# BpodFSM_r2_1.net
KiCad netlist of a schematic drawn in EAGLE
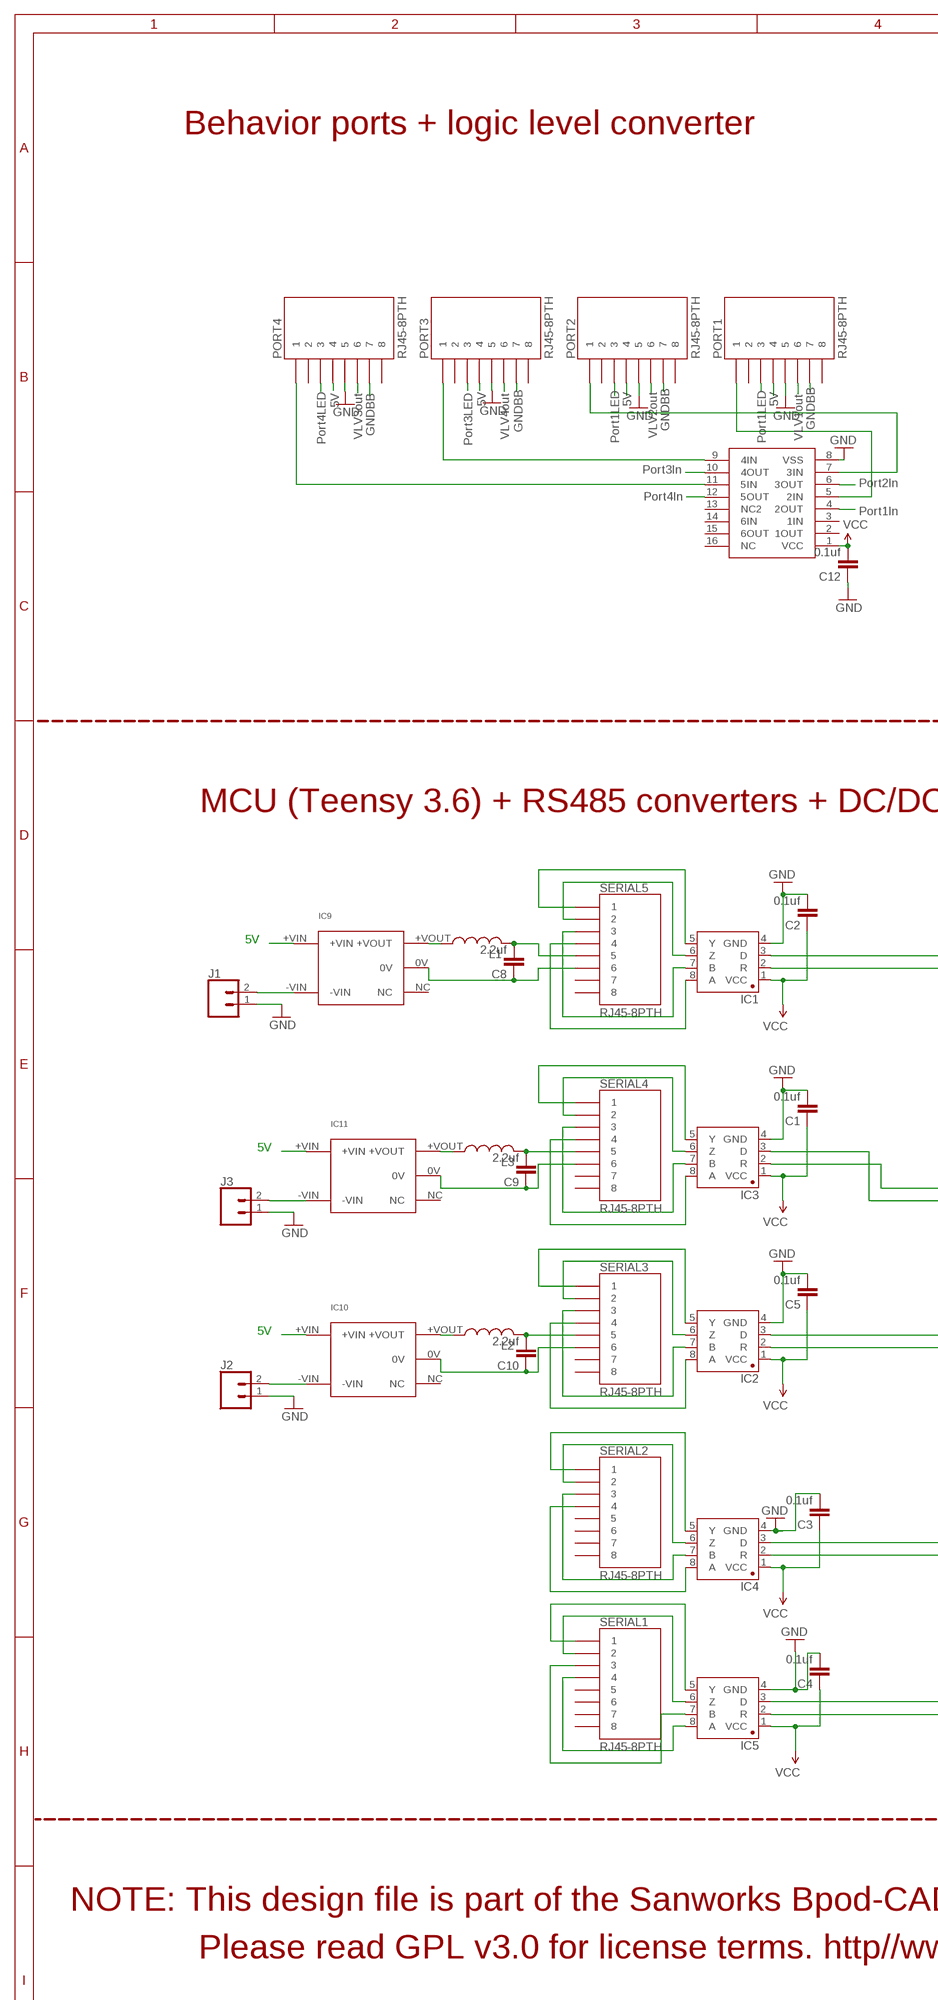
[diagram p0: schematic, sheet 1, part 1 of 2]
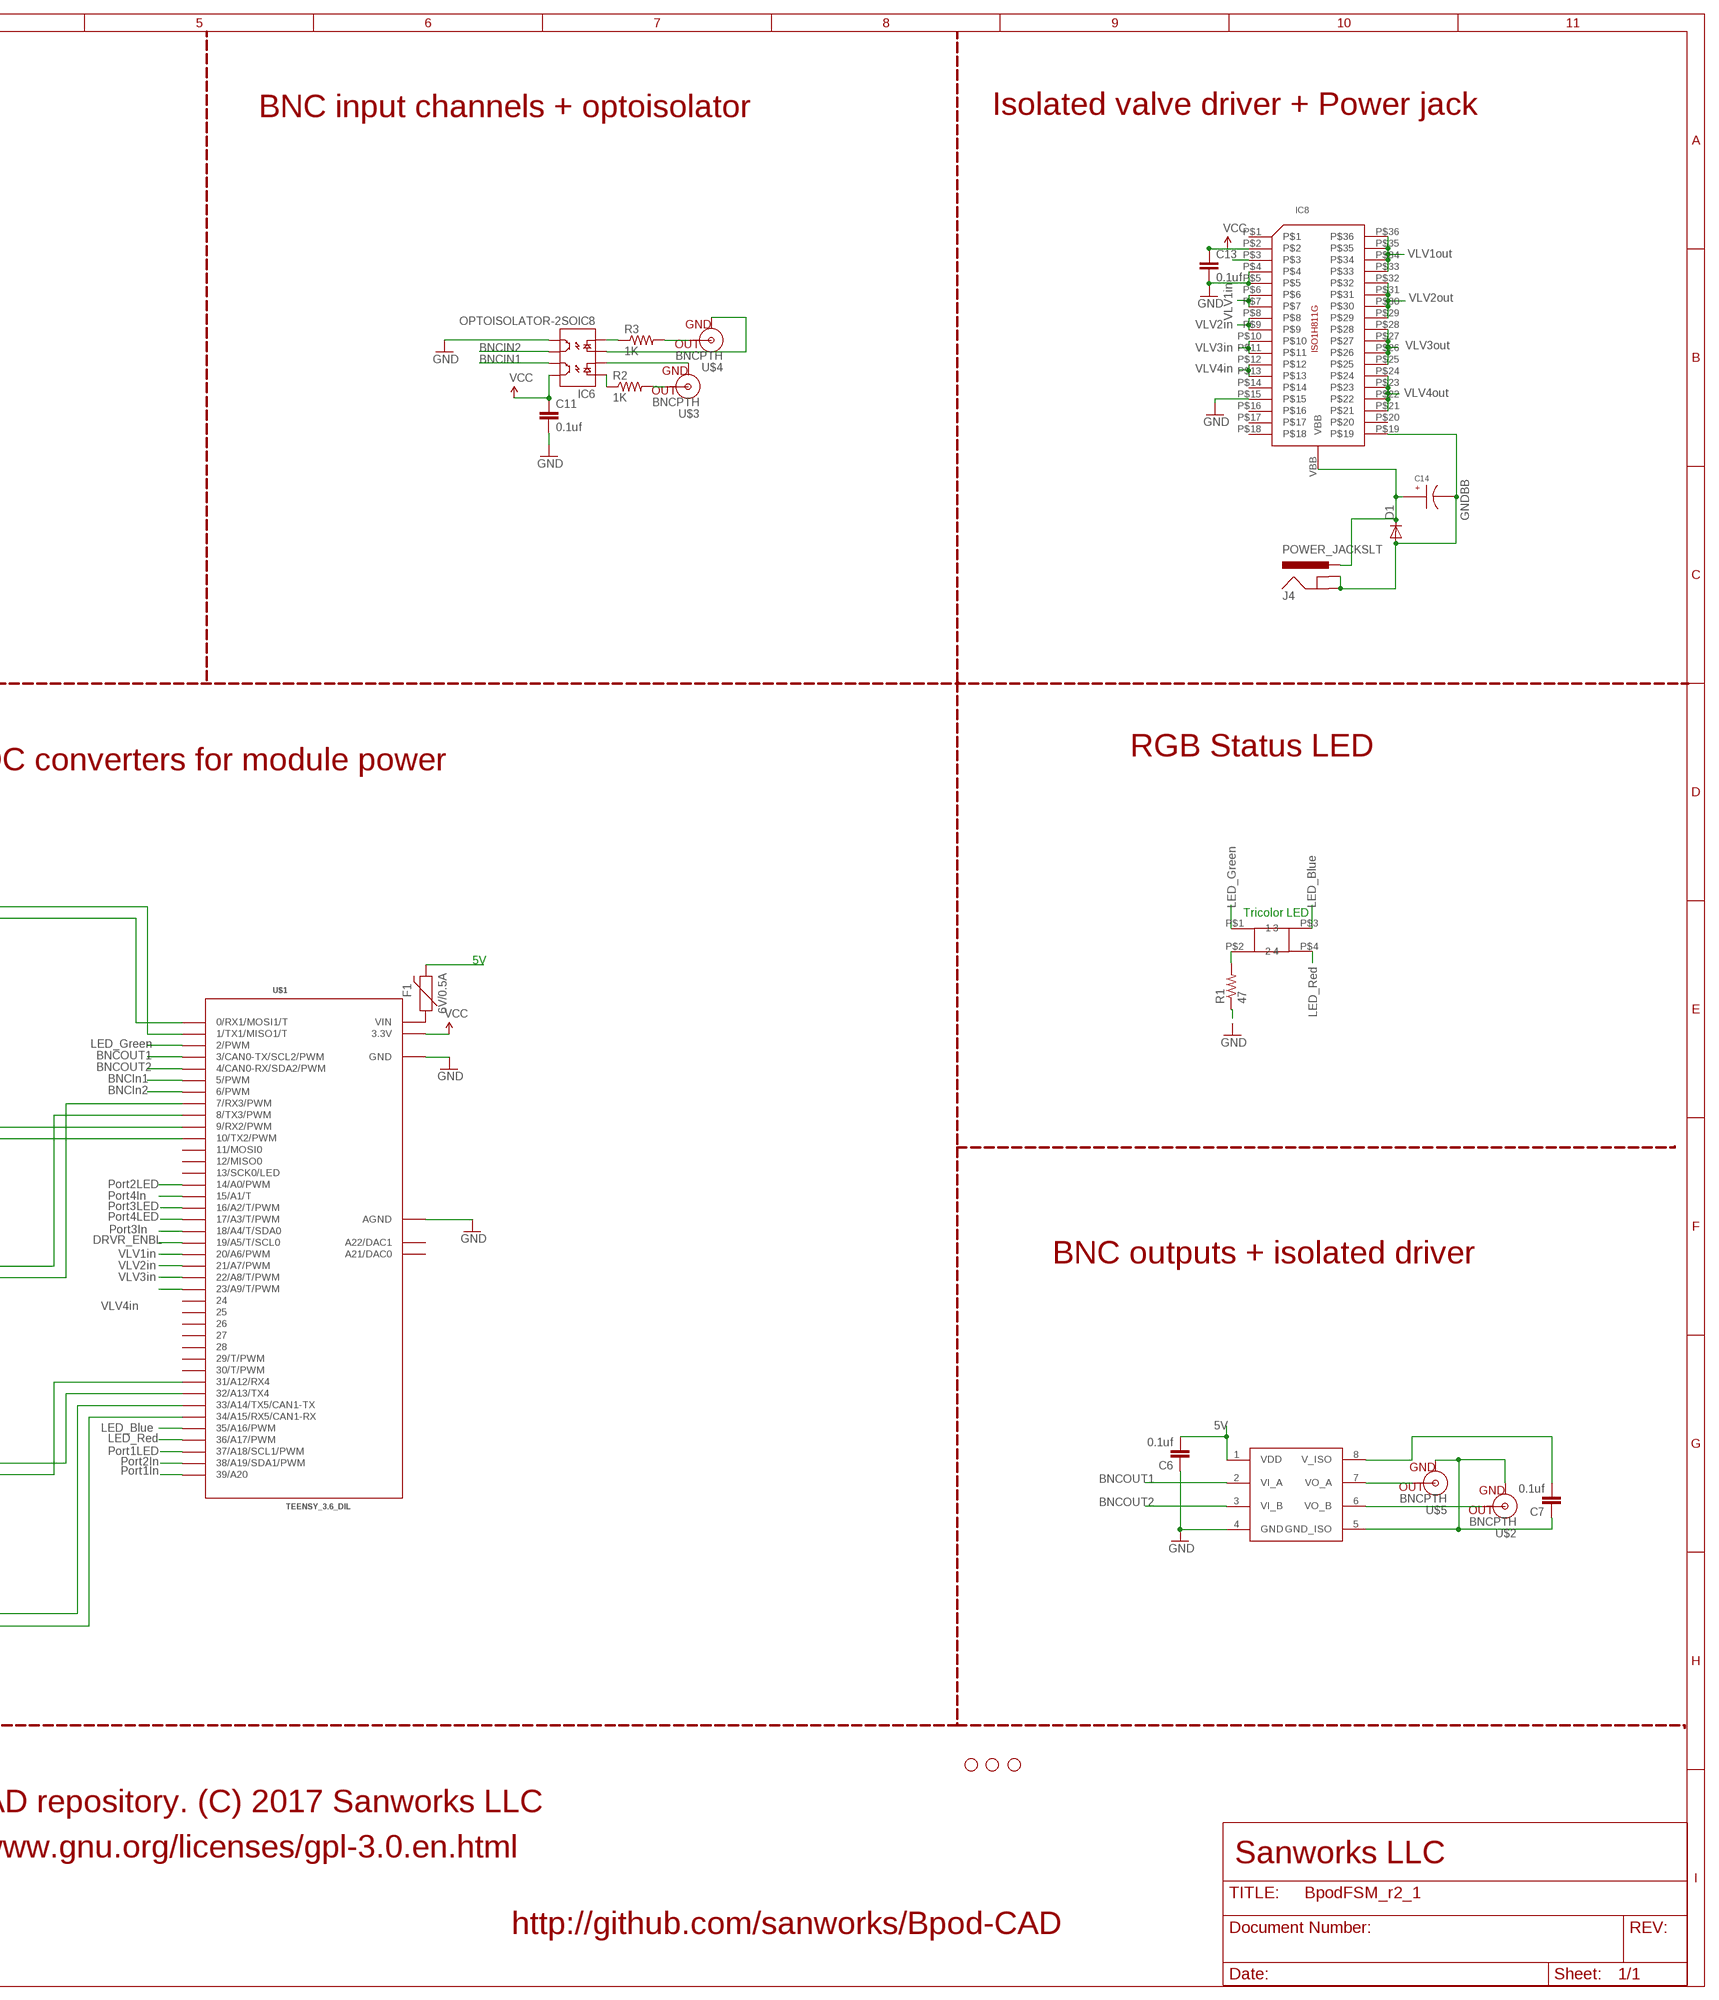
[diagram p1: schematic, sheet 1, part 2 of 2]

(export (version "E")
  (design (tool "Eeschema 10.0.6"))
  (components
    (comp (ref "C1")
      (value "0.1uf")
      (footprint "eagle-import:1206")
      (libsource (lib "eagle-import") (part "CAP1206"))
    )
    (comp (ref "C2")
      (value "0.1uf")
      (footprint "eagle-import:1206")
      (libsource (lib "eagle-import") (part "CAP1206"))
    )
    (comp (ref "C3")
      (value "0.1uf")
      (footprint "eagle-import:1206")
      (libsource (lib "eagle-import") (part "CAP1206"))
    )
    (comp (ref "C4")
      (value "0.1uf")
      (footprint "eagle-import:1206")
      (libsource (lib "eagle-import") (part "CAP1206"))
    )
    (comp (ref "C5")
      (value "0.1uf")
      (footprint "eagle-import:1206")
      (libsource (lib "eagle-import") (part "CAP1206"))
    )
    (comp (ref "C6")
      (value "0.1uf")
      (footprint "eagle-import:1206")
      (libsource (lib "eagle-import") (part "CAP1206"))
    )
    (comp (ref "C7")
      (value "0.1uf")
      (footprint "eagle-import:1206")
      (libsource (lib "eagle-import") (part "CAP1206"))
    )
    (comp (ref "C8")
      (value "2.2uf")
      (footprint "eagle-import:1206")
      (libsource (lib "eagle-import") (part "CAP1206"))
    )
    (comp (ref "C9")
      (value "2.2uf")
      (footprint "eagle-import:1206")
      (libsource (lib "eagle-import") (part "CAP1206"))
    )
    (comp (ref "C10")
      (value "2.2uf")
      (footprint "eagle-import:1206")
      (libsource (lib "eagle-import") (part "CAP1206"))
    )
    (comp (ref "C11")
      (value "0.1uf")
      (footprint "eagle-import:1206")
      (libsource (lib "eagle-import") (part "CAP1206"))
    )
    (comp (ref "C12")
      (value "0.1uf")
      (footprint "eagle-import:1206")
      (libsource (lib "eagle-import") (part "CAP1206"))
    )
    (comp (ref "C13")
      (value "0.1uf")
      (footprint "eagle-import:1206")
      (libsource (lib "eagle-import") (part "CAP1206"))
    )
    (comp (ref "C14")
      (value "EEE-FK1H100UR")
      (footprint "eagle-import:EEE-FK1H100UR")
      (libsource (lib "eagle-import") (part "EEE-FK1H100UR"))
    )
    (comp (ref "D1")
      (value "DIODE-DO214AA")
      (footprint "eagle-import:DO214AA")
      (libsource (lib "eagle-import") (part "DIODE-DO214AA"))
    )
    (comp (ref "F1")
      (value "6V/0.5A")
      (footprint "eagle-import:1206")
      (libsource (lib "eagle-import") (part "PPTC_HALF-AMP"))
    )
    (comp (ref "IC1")
      (value "SN65HVD31DR")
      (footprint "eagle-import:SO08")
      (libsource (lib "eagle-import") (part "SN65HVD31DR"))
    )
    (comp (ref "IC2")
      (value "SN65HVD31DR")
      (footprint "eagle-import:SO08")
      (libsource (lib "eagle-import") (part "SN65HVD31DR"))
    )
    (comp (ref "IC3")
      (value "SN65HVD31DR")
      (footprint "eagle-import:SO08")
      (libsource (lib "eagle-import") (part "SN65HVD31DR"))
    )
    (comp (ref "IC4")
      (value "SN65HVD31DR")
      (footprint "eagle-import:SO08")
      (libsource (lib "eagle-import") (part "SN65HVD31DR"))
    )
    (comp (ref "IC5")
      (value "SN65HVD31DR")
      (footprint "eagle-import:SO08")
      (libsource (lib "eagle-import") (part "SN65HVD31DR"))
    )
    (comp (ref "IC6")
      (value "OPTOISOLATOR-2SOIC8")
      (footprint "eagle-import:SO08-2")
      (libsource (lib "eagle-import") (part "OPTOISOLATOR-2SOIC8"))
    )
    (comp (ref "IC7")
      (value "ADUM5240")
      (footprint "eagle-import:SO08")
      (libsource (lib "eagle-import") (part "ADUM5240"))
    )
    (comp (ref "IC8")
      (value "ISO1H811G")
      (footprint "eagle-import:ISO1H811G")
      (libsource (lib "eagle-import") (part "ISO1H811G"))
    )
    (comp (ref "IC9")
      (value "MTU1D0505MC")
      (footprint "eagle-import:MTU1D0505MC")
      (libsource (lib "eagle-import") (part "MTU1D0505MC"))
    )
    (comp (ref "IC10")
      (value "MTU1D0505MC")
      (footprint "eagle-import:MTU1D0505MC")
      (libsource (lib "eagle-import") (part "MTU1D0505MC"))
    )
    (comp (ref "IC11")
      (value "MTU1D0505MC")
      (footprint "eagle-import:MTU1D0505MC")
      (libsource (lib "eagle-import") (part "MTU1D0505MC"))
    )
    (comp (ref "IC12")
      (value "CD4050")
      (footprint "eagle-import:SO16")
      (libsource (lib "eagle-import") (part "CD4050"))
    )
    (comp (ref "J1")
      (value "CONN_02")
      (footprint "eagle-import:1X02")
      (libsource (lib "eagle-import") (part "CONN_02"))
    )
    (comp (ref "J2")
      (value "CONN_02")
      (footprint "eagle-import:1X02")
      (libsource (lib "eagle-import") (part "CONN_02"))
    )
    (comp (ref "J3")
      (value "CONN_02")
      (footprint "eagle-import:1X02")
      (libsource (lib "eagle-import") (part "CONN_02"))
    )
    (comp (ref "J4")
      (value "POWER_JACKSLT")
      (footprint "eagle-import:POWER_JACK_SLOT")
      (libsource (lib "eagle-import") (part "POWER_JACKSLT"))
    )
    (comp (ref "JP3")
      (value "STAND-OFF")
      (footprint "eagle-import:STAND-OFF")
      (libsource (lib "eagle-import") (part "STAND-OFF"))
    )
    (comp (ref "JP4")
      (value "STAND-OFF")
      (footprint "eagle-import:STAND-OFF")
      (libsource (lib "eagle-import") (part "STAND-OFF"))
    )
    (comp (ref "JP5")
      (value "STAND-OFF")
      (footprint "eagle-import:STAND-OFF")
      (libsource (lib "eagle-import") (part "STAND-OFF"))
    )
    (comp (ref "L1")
      (value "L-USL3225M")
      (footprint "eagle-import:L3225M")
      (libsource (lib "eagle-import") (part "L-USL3225M"))
    )
    (comp (ref "L2")
      (value "L-USL3225M")
      (footprint "eagle-import:L3225M")
      (libsource (lib "eagle-import") (part "L-USL3225M"))
    )
    (comp (ref "L3")
      (value "L-USL3225M")
      (footprint "eagle-import:L3225M")
      (libsource (lib "eagle-import") (part "L-USL3225M"))
    )
    (comp (ref "PORT1")
      (value "RJ45-8PTH")
      (footprint "eagle-import:RJ45-8")
      (libsource (lib "eagle-import") (part "RJ45-8PTH"))
    )
    (comp (ref "PORT2")
      (value "RJ45-8PTH")
      (footprint "eagle-import:RJ45-8")
      (libsource (lib "eagle-import") (part "RJ45-8PTH"))
    )
    (comp (ref "PORT3")
      (value "RJ45-8PTH")
      (footprint "eagle-import:RJ45-8")
      (libsource (lib "eagle-import") (part "RJ45-8PTH"))
    )
    (comp (ref "PORT4")
      (value "RJ45-8PTH")
      (footprint "eagle-import:RJ45-8")
      (libsource (lib "eagle-import") (part "RJ45-8PTH"))
    )
    (comp (ref "R1")
      (value "47")
      (footprint "eagle-import:1206")
      (libsource (lib "eagle-import") (part "RESISTOR1206"))
    )
    (comp (ref "R2")
      (value "1K")
      (footprint "eagle-import:1206")
      (libsource (lib "eagle-import") (part "SparkFun-Resistors_RESISTOR1206"))
    )
    (comp (ref "R3")
      (value "1K")
      (footprint "eagle-import:1206")
      (libsource (lib "eagle-import") (part "SparkFun-Resistors_RESISTOR1206"))
    )
    (comp (ref "SERIAL1")
      (value "RJ45-8PTH")
      (footprint "eagle-import:RJ45-8")
      (libsource (lib "eagle-import") (part "RJ45-8PTH"))
    )
    (comp (ref "SERIAL2")
      (value "RJ45-8PTH")
      (footprint "eagle-import:RJ45-8")
      (libsource (lib "eagle-import") (part "RJ45-8PTH"))
    )
    (comp (ref "SERIAL3")
      (value "RJ45-8PTH")
      (footprint "eagle-import:RJ45-8")
      (libsource (lib "eagle-import") (part "RJ45-8PTH"))
    )
    (comp (ref "SERIAL4")
      (value "RJ45-8PTH")
      (footprint "eagle-import:RJ45-8")
      (libsource (lib "eagle-import") (part "RJ45-8PTH"))
    )
    (comp (ref "SERIAL5")
      (value "RJ45-8PTH")
      (footprint "eagle-import:RJ45-8")
      (libsource (lib "eagle-import") (part "RJ45-8PTH"))
    )
    (comp (ref "U$1")
      (value "TEENSY_3.6_DIL")
      (footprint "eagle-import:TEENSY_3.6_DIL")
      (libsource (lib "eagle-import") (part "TEENSY_3.6_DIL"))
    )
    (comp (ref "U$2")
      (value "BNCPTH")
      (footprint "eagle-import:BNC")
      (libsource (lib "eagle-import") (part "BNCPTH"))
    )
    (comp (ref "U$3")
      (value "BNCPTH")
      (footprint "eagle-import:BNC")
      (libsource (lib "eagle-import") (part "BNCPTH"))
    )
    (comp (ref "U$4")
      (value "BNCPTH")
      (footprint "eagle-import:BNC")
      (libsource (lib "eagle-import") (part "BNCPTH"))
    )
    (comp (ref "U$5")
      (value "BNCPTH")
      (footprint "eagle-import:BNC")
      (libsource (lib "eagle-import") (part "BNCPTH"))
    )
    (comp (ref "U$8")
      (value "SQUARE_TRICOLOR_LED")
      (footprint "eagle-import:SQUARE_TRICOLOR_LED")
      (libsource (lib "eagle-import") (part "SQUARE_TRICOLOR_LED"))
    )
  )
  (nets
    (net (code "1") (name "/5V") (class "Default")
      (node (ref "C6") (pin "2") (pinfunction "2_2") (pintype "passive"))
      (node (ref "F1") (pin "2") (pinfunction "2_2") (pintype "bidirectional"))
      (node (ref "IC10") (pin "+VIN") (pinfunction "+VIN_+VIN") (pintype "bidirectional"))
      (node (ref "IC11") (pin "+VIN") (pinfunction "+VIN_+VIN") (pintype "bidirectional"))
      (node (ref "IC7") (pin "1") (pinfunction "VDD_1") (pintype "bidirectional"))
      (node (ref "IC9") (pin "+VIN") (pinfunction "+VIN_+VIN") (pintype "bidirectional"))
      (node (ref "PORT1") (pin "4") (pinfunction "4_4") (pintype "bidirectional"))
      (node (ref "PORT2") (pin "4") (pinfunction "4_4") (pintype "bidirectional"))
      (node (ref "PORT3") (pin "4") (pinfunction "4_4") (pintype "bidirectional"))
      (node (ref "PORT4") (pin "4") (pinfunction "4_4") (pintype "bidirectional"))
    )
    (net (code "2") (name "/BNCIN1") (class "Default")
      (node (ref "IC6") (pin "7") (pinfunction "EM1_7") (pintype "bidirectional"))
      (node (ref "U$1") (pin "6") (pinfunction "6/PWM_6") (pintype "bidirectional"))
    )
    (net (code "3") (name "/BNCIN2") (class "Default")
      (node (ref "IC6") (pin "6") (pinfunction "CL2_6") (pintype "bidirectional"))
      (node (ref "U$1") (pin "5") (pinfunction "5/PWM_5") (pintype "bidirectional"))
    )
    (net (code "4") (name "/BNCOUT1") (class "Default")
      (node (ref "IC7") (pin "3") (pinfunction "VI_B_3") (pintype "bidirectional"))
      (node (ref "U$1") (pin "4") (pinfunction "4/CAN0-RX/SDA2/PWM_4") (pintype "bidirectional"))
    )
    (net (code "5") (name "/BNCOUT2") (class "Default")
      (node (ref "IC7") (pin "2") (pinfunction "VI_A_2") (pintype "bidirectional"))
      (node (ref "U$1") (pin "3") (pinfunction "3/CAN0-TX/SCL2/PWM_3") (pintype "bidirectional"))
    )
    (net (code "6") (name "/DRVR_ENBL") (class "Default")
      (node (ref "IC8") (pin "P$3") (pinfunction "P$3_P$3") (pintype "bidirectional"))
      (node (ref "U$1") (pin "19/A5") (pinfunction "19/A5/T/SCL0_19/A5") (pintype "bidirectional"))
    )
    (net (code "7") (name "/GNDBB") (class "Default")
      (node (ref "C14") (pin "CATHODE") (pinfunction "CATHODE_CATHODE") (pintype "bidirectional"))
      (node (ref "D1") (pin "A") (pinfunction "A_A") (pintype "passive"))
      (node (ref "IC8") (pin "P$19") (pinfunction "P$19_P$19") (pintype "bidirectional"))
      (node (ref "J4") (pin "GND@1") (pinfunction "GNDBREAK_GND@1") (pintype "bidirectional"))
      (node (ref "J4") (pin "GND@2") (pinfunction "GND_GND@2") (pintype "bidirectional"))
      (node (ref "PORT1") (pin "7") (pinfunction "7_7") (pintype "bidirectional"))
      (node (ref "PORT2") (pin "7") (pinfunction "7_7") (pintype "bidirectional"))
      (node (ref "PORT3") (pin "7") (pinfunction "7_7") (pintype "bidirectional"))
      (node (ref "PORT4") (pin "7") (pinfunction "7_7") (pintype "bidirectional"))
    )
    (net (code "8") (name "/LED_BLUE") (class "Default")
      (node (ref "U$1") (pin "35/A16") (pinfunction "35/A16/PWM_35/A16") (pintype "bidirectional"))
      (node (ref "U$8") (pin "P$3") (pinfunction "3_P$3") (pintype "bidirectional"))
    )
    (net (code "9") (name "/LED_GREEN") (class "Default")
      (node (ref "U$1") (pin "2") (pinfunction "2/PWM_2") (pintype "bidirectional"))
      (node (ref "U$8") (pin "P$1") (pinfunction "1_P$1") (pintype "bidirectional"))
    )
    (net (code "10") (name "/LED_RED") (class "Default")
      (node (ref "U$1") (pin "36/A17") (pinfunction "36/A17/PWM_36/A17") (pintype "bidirectional"))
      (node (ref "U$8") (pin "P$4") (pinfunction "4_P$4") (pintype "bidirectional"))
    )
    (net (code "11") (name "/PORT1IN") (class "Default")
      (node (ref "IC12") (pin "4") (pinfunction "2OUT_4") (pintype "bidirectional"))
      (node (ref "U$1") (pin "39/A20") (pinfunction "39/A20_39/A20") (pintype "bidirectional"))
    )
    (net (code "12") (name "/PORT1LED") (class "Default")
      (node (ref "PORT1") (pin "3") (pinfunction "3_3") (pintype "bidirectional"))
      (node (ref "U$1") (pin "37/A18") (pinfunction "37/A18/SCL1/PWM_37/A18") (pintype "bidirectional"))
    )
    (net (code "13") (name "/PORT2IN") (class "Default")
      (node (ref "IC12") (pin "6") (pinfunction "3OUT_6") (pintype "bidirectional"))
      (node (ref "U$1") (pin "38/A19") (pinfunction "38/A19/SDA1/PWM_38/A19") (pintype "bidirectional"))
    )
    (net (code "14") (name "/PORT2LED") (class "Default")
      (node (ref "PORT2") (pin "3") (pinfunction "3_3") (pintype "bidirectional"))
      (node (ref "U$1") (pin "14/A0") (pinfunction "14/A0/PWM_14/A0") (pintype "bidirectional"))
    )
    (net (code "15") (name "/PORT3IN") (class "Default")
      (node (ref "IC12") (pin "10") (pinfunction "4OUT_10") (pintype "bidirectional"))
      (node (ref "U$1") (pin "18/A4") (pinfunction "18/A4/T/SDA0_18/A4") (pintype "bidirectional"))
    )
    (net (code "16") (name "/PORT3LED") (class "Default")
      (node (ref "PORT3") (pin "3") (pinfunction "3_3") (pintype "bidirectional"))
      (node (ref "U$1") (pin "16/A2") (pinfunction "16/A2/T/PWM_16/A2") (pintype "bidirectional"))
    )
    (net (code "17") (name "/PORT4IN") (class "Default")
      (node (ref "IC12") (pin "12") (pinfunction "5OUT_12") (pintype "bidirectional"))
      (node (ref "U$1") (pin "15/A1") (pinfunction "15/A1/T_15/A1") (pintype "bidirectional"))
    )
    (net (code "18") (name "/PORT4LED") (class "Default")
      (node (ref "PORT4") (pin "3") (pinfunction "3_3") (pintype "bidirectional"))
      (node (ref "U$1") (pin "17/A3") (pinfunction "17/A3/T/PWM_17/A3") (pintype "bidirectional"))
    )
    (net (code "19") (name "/VLV1IN") (class "Default")
      (node (ref "IC8") (pin "P$6") (pinfunction "P$6_P$6") (pintype "bidirectional"))
      (node (ref "IC8") (pin "P$7") (pinfunction "P$7_P$7") (pintype "bidirectional"))
      (node (ref "U$1") (pin "23/A9") (pinfunction "23/A9/T/PWM_23/A9") (pintype "bidirectional"))
    )
    (net (code "20") (name "/VLV1OUT") (class "Default")
      (node (ref "IC8") (pin "P$33") (pinfunction "P$33_P$33") (pintype "bidirectional"))
      (node (ref "IC8") (pin "P$34") (pinfunction "P$34_P$34") (pintype "bidirectional"))
      (node (ref "IC8") (pin "P$35") (pinfunction "P$35_P$35") (pintype "bidirectional"))
      (node (ref "IC8") (pin "P$36") (pinfunction "P$36_P$36") (pintype "bidirectional"))
      (node (ref "PORT1") (pin "6") (pinfunction "6_6") (pintype "bidirectional"))
    )
    (net (code "21") (name "/VLV2IN") (class "Default")
      (node (ref "IC8") (pin "P$8") (pinfunction "P$8_P$8") (pintype "bidirectional"))
      (node (ref "IC8") (pin "P$9") (pinfunction "P$9_P$9") (pintype "bidirectional"))
      (node (ref "U$1") (pin "22/A8") (pinfunction "22/A8/T/PWM_22/A8") (pintype "bidirectional"))
    )
    (net (code "22") (name "/VLV2OUT") (class "Default")
      (node (ref "IC8") (pin "P$29") (pinfunction "P$29_P$29") (pintype "bidirectional"))
      (node (ref "IC8") (pin "P$30") (pinfunction "P$30_P$30") (pintype "bidirectional"))
      (node (ref "IC8") (pin "P$31") (pinfunction "P$31_P$31") (pintype "bidirectional"))
      (node (ref "IC8") (pin "P$32") (pinfunction "P$32_P$32") (pintype "bidirectional"))
      (node (ref "PORT2") (pin "6") (pinfunction "6_6") (pintype "bidirectional"))
    )
    (net (code "23") (name "/VLV3IN") (class "Default")
      (node (ref "IC8") (pin "P$12") (pinfunction "P$12_P$12") (pintype "bidirectional"))
      (node (ref "IC8") (pin "P$13") (pinfunction "P$13_P$13") (pintype "bidirectional"))
      (node (ref "U$1") (pin "20/A6") (pinfunction "20/A6/PWM_20/A6") (pintype "bidirectional"))
    )
    (net (code "24") (name "/VLV3OUT") (class "Default")
      (node (ref "IC8") (pin "P$21") (pinfunction "P$21_P$21") (pintype "bidirectional"))
      (node (ref "IC8") (pin "P$22") (pinfunction "P$22_P$22") (pintype "bidirectional"))
      (node (ref "IC8") (pin "P$23") (pinfunction "P$23_P$23") (pintype "bidirectional"))
      (node (ref "IC8") (pin "P$24") (pinfunction "P$24_P$24") (pintype "bidirectional"))
      (node (ref "PORT3") (pin "6") (pinfunction "6_6") (pintype "bidirectional"))
    )
    (net (code "25") (name "/VLV4IN") (class "Default")
      (node (ref "IC8") (pin "P$10") (pinfunction "P$10_P$10") (pintype "bidirectional"))
      (node (ref "IC8") (pin "P$11") (pinfunction "P$11_P$11") (pintype "bidirectional"))
      (node (ref "U$1") (pin "21/A7") (pinfunction "21/A7/PWM_21/A7") (pintype "bidirectional"))
    )
    (net (code "26") (name "/VLV4OUT") (class "Default")
      (node (ref "IC8") (pin "P$25") (pinfunction "P$25_P$25") (pintype "bidirectional"))
      (node (ref "IC8") (pin "P$26") (pinfunction "P$26_P$26") (pintype "bidirectional"))
      (node (ref "IC8") (pin "P$27") (pinfunction "P$27_P$27") (pintype "bidirectional"))
      (node (ref "IC8") (pin "P$28") (pinfunction "P$28_P$28") (pintype "bidirectional"))
      (node (ref "PORT4") (pin "6") (pinfunction "6_6") (pintype "bidirectional"))
    )
    (net (code "27") (name "GND") (class "Default")
      (node (ref "C1") (pin "2") (pinfunction "2_2") (pintype "passive"))
      (node (ref "C11") (pin "2") (pinfunction "2_2") (pintype "passive"))
      (node (ref "C12") (pin "1") (pinfunction "1_1") (pintype "passive"))
      (node (ref "C13") (pin "2") (pinfunction "2_2") (pintype "passive"))
      (node (ref "C2") (pin "2") (pinfunction "2_2") (pintype "passive"))
      (node (ref "C3") (pin "2") (pinfunction "2_2") (pintype "passive"))
      (node (ref "C4") (pin "2") (pinfunction "2_2") (pintype "passive"))
      (node (ref "C5") (pin "2") (pinfunction "2_2") (pintype "passive"))
      (node (ref "C6") (pin "1") (pinfunction "1_1") (pintype "passive"))
      (node (ref "IC1") (pin "4") (pinfunction "GND_4") (pintype "bidirectional"))
      (node (ref "IC12") (pin "8") (pinfunction "VSS_8") (pintype "bidirectional"))
      (node (ref "IC2") (pin "4") (pinfunction "GND_4") (pintype "bidirectional"))
      (node (ref "IC3") (pin "4") (pinfunction "GND_4") (pintype "bidirectional"))
      (node (ref "IC4") (pin "4") (pinfunction "GND_4") (pintype "bidirectional"))
      (node (ref "IC5") (pin "4") (pinfunction "GND_4") (pintype "bidirectional"))
      (node (ref "IC6") (pin "5") (pinfunction "EM2_5") (pintype "bidirectional"))
      (node (ref "IC7") (pin "4") (pinfunction "GND_4") (pintype "bidirectional"))
      (node (ref "IC8") (pin "P$15") (pinfunction "P$15_P$15") (pintype "bidirectional"))
      (node (ref "IC8") (pin "P$4") (pinfunction "P$4_P$4") (pintype "bidirectional"))
      (node (ref "IC8") (pin "P$5") (pinfunction "P$5_P$5") (pintype "bidirectional"))
      (node (ref "J1") (pin "1") (pinfunction "1_1") (pintype "passive"))
      (node (ref "J2") (pin "1") (pinfunction "1_1") (pintype "passive"))
      (node (ref "J3") (pin "1") (pinfunction "1_1") (pintype "passive"))
      (node (ref "PORT1") (pin "5") (pinfunction "5_5") (pintype "bidirectional"))
      (node (ref "PORT2") (pin "5") (pinfunction "5_5") (pintype "bidirectional"))
      (node (ref "PORT3") (pin "5") (pinfunction "5_5") (pintype "bidirectional"))
      (node (ref "PORT4") (pin "5") (pinfunction "5_5") (pintype "bidirectional"))
      (node (ref "R1") (pin "1") (pinfunction "1_1") (pintype "passive"))
      (node (ref "U$1") (pin "AGND") (pinfunction "AGND_AGND") (pintype "power_in"))
      (node (ref "U$1") (pin "GND") (pinfunction "GND_GND") (pintype "power_in"))
      (node (ref "U$1") (pin "GND1") (pinfunction "GND_GND1") (pintype "power_in"))
    )
    (net (code "28") (name "Net-(C8-Pad1)") (class "Default")
      (node (ref "C8") (pin "1") (pinfunction "1_1") (pintype "passive"))
      (node (ref "IC9") (pin "0V") (pinfunction "0V_0V") (pintype "bidirectional"))
      (node (ref "SERIAL5") (pin "6") (pinfunction "6_6") (pintype "bidirectional"))
    )
    (net (code "29") (name "Net-(C8-Pad2)") (class "Default")
      (node (ref "C8") (pin "2") (pinfunction "2_2") (pintype "passive"))
      (node (ref "L1") (pin "2") (pinfunction "2_2") (pintype "passive"))
      (node (ref "SERIAL5") (pin "5") (pinfunction "5_5") (pintype "bidirectional"))
    )
    (net (code "30") (name "Net-(C9-Pad1)") (class "Default")
      (node (ref "C9") (pin "1") (pinfunction "1_1") (pintype "passive"))
      (node (ref "IC11") (pin "0V") (pinfunction "0V_0V") (pintype "bidirectional"))
      (node (ref "SERIAL4") (pin "6") (pinfunction "6_6") (pintype "bidirectional"))
    )
    (net (code "31") (name "Net-(C9-Pad2)") (class "Default")
      (node (ref "C9") (pin "2") (pinfunction "2_2") (pintype "passive"))
      (node (ref "L3") (pin "2") (pinfunction "2_2") (pintype "passive"))
      (node (ref "SERIAL4") (pin "5") (pinfunction "5_5") (pintype "bidirectional"))
    )
    (net (code "32") (name "Net-(C10-Pad1)") (class "Default")
      (node (ref "C10") (pin "1") (pinfunction "1_1") (pintype "passive"))
      (node (ref "IC10") (pin "0V") (pinfunction "0V_0V") (pintype "bidirectional"))
      (node (ref "SERIAL3") (pin "6") (pinfunction "6_6") (pintype "bidirectional"))
    )
    (net (code "33") (name "Net-(C10-Pad2)") (class "Default")
      (node (ref "C10") (pin "2") (pinfunction "2_2") (pintype "passive"))
      (node (ref "L2") (pin "2") (pinfunction "2_2") (pintype "passive"))
      (node (ref "SERIAL3") (pin "5") (pinfunction "5_5") (pintype "bidirectional"))
    )
    (net (code "34") (name "Net-(C14-PadANODE)") (class "Default")
      (node (ref "C14") (pin "ANODE") (pinfunction "ANODE_ANODE") (pintype "bidirectional"))
      (node (ref "D1") (pin "C") (pinfunction "C_C") (pintype "passive"))
      (node (ref "IC8") (pin "VBB") (pinfunction "VBB_VBB") (pintype "bidirectional"))
      (node (ref "J4") (pin "PWR") (pinfunction "PWR_PWR") (pintype "bidirectional"))
    )
    (net (code "35") (name "Net-(F1-Pad1)") (class "Default")
      (node (ref "F1") (pin "1") (pinfunction "1_1") (pintype "bidirectional"))
      (node (ref "U$1") (pin "VIN") (pinfunction "VIN_VIN") (pintype "power_in"))
    )
    (net (code "36") (name "Net-(IC1-A)") (class "Default")
      (node (ref "IC1") (pin "8") (pinfunction "A_8") (pintype "bidirectional"))
      (node (ref "SERIAL5") (pin "4") (pinfunction "4_4") (pintype "bidirectional"))
    )
    (net (code "37") (name "Net-(IC1-B)") (class "Default")
      (node (ref "IC1") (pin "7") (pinfunction "B_7") (pintype "bidirectional"))
      (node (ref "SERIAL5") (pin "3") (pinfunction "3_3") (pintype "bidirectional"))
    )
    (net (code "38") (name "Net-(IC1-D)") (class "Default")
      (node (ref "IC1") (pin "3") (pinfunction "D_3") (pintype "bidirectional"))
      (node (ref "U$1") (pin "1") (pinfunction "1/TX1/MISO1/T_1") (pintype "bidirectional"))
    )
    (net (code "39") (name "Net-(IC1-R)") (class "Default")
      (node (ref "IC1") (pin "2") (pinfunction "R_2") (pintype "bidirectional"))
      (node (ref "U$1") (pin "0") (pinfunction "0/RX1/MOSI1/T_0") (pintype "bidirectional"))
    )
    (net (code "40") (name "Net-(IC1-Y)") (class "Default")
      (node (ref "IC1") (pin "5") (pinfunction "Y_5") (pintype "bidirectional"))
      (node (ref "SERIAL5") (pin "1") (pinfunction "1_1") (pintype "bidirectional"))
    )
    (net (code "41") (name "Net-(IC1-Z)") (class "Default")
      (node (ref "IC1") (pin "6") (pinfunction "Z_6") (pintype "bidirectional"))
      (node (ref "SERIAL5") (pin "2") (pinfunction "2_2") (pintype "bidirectional"))
    )
    (net (code "42") (name "Net-(IC2-A)") (class "Default")
      (node (ref "IC2") (pin "8") (pinfunction "A_8") (pintype "bidirectional"))
      (node (ref "SERIAL3") (pin "4") (pinfunction "4_4") (pintype "bidirectional"))
    )
    (net (code "43") (name "Net-(IC2-B)") (class "Default")
      (node (ref "IC2") (pin "7") (pinfunction "B_7") (pintype "bidirectional"))
      (node (ref "SERIAL3") (pin "3") (pinfunction "3_3") (pintype "bidirectional"))
    )
    (net (code "44") (name "Net-(IC2-D)") (class "Default")
      (node (ref "IC2") (pin "3") (pinfunction "D_3") (pintype "bidirectional"))
      (node (ref "U$1") (pin "8") (pinfunction "8/TX3/PWM_8") (pintype "bidirectional"))
    )
    (net (code "45") (name "Net-(IC2-R)") (class "Default")
      (node (ref "IC2") (pin "2") (pinfunction "R_2") (pintype "bidirectional"))
      (node (ref "U$1") (pin "7") (pinfunction "7/RX3/PWM_7") (pintype "bidirectional"))
    )
    (net (code "46") (name "Net-(IC2-Y)") (class "Default")
      (node (ref "IC2") (pin "5") (pinfunction "Y_5") (pintype "bidirectional"))
      (node (ref "SERIAL3") (pin "1") (pinfunction "1_1") (pintype "bidirectional"))
    )
    (net (code "47") (name "Net-(IC2-Z)") (class "Default")
      (node (ref "IC2") (pin "6") (pinfunction "Z_6") (pintype "bidirectional"))
      (node (ref "SERIAL3") (pin "2") (pinfunction "2_2") (pintype "bidirectional"))
    )
    (net (code "48") (name "Net-(IC3-A)") (class "Default")
      (node (ref "IC3") (pin "8") (pinfunction "A_8") (pintype "bidirectional"))
      (node (ref "SERIAL4") (pin "4") (pinfunction "4_4") (pintype "bidirectional"))
    )
    (net (code "49") (name "Net-(IC3-B)") (class "Default")
      (node (ref "IC3") (pin "7") (pinfunction "B_7") (pintype "bidirectional"))
      (node (ref "SERIAL4") (pin "3") (pinfunction "3_3") (pintype "bidirectional"))
    )
    (net (code "50") (name "Net-(IC3-D)") (class "Default")
      (node (ref "IC3") (pin "3") (pinfunction "D_3") (pintype "bidirectional"))
      (node (ref "U$1") (pin "10") (pinfunction "10/TX2/PWM_10") (pintype "bidirectional"))
    )
    (net (code "51") (name "Net-(IC3-R)") (class "Default")
      (node (ref "IC3") (pin "2") (pinfunction "R_2") (pintype "bidirectional"))
      (node (ref "U$1") (pin "9") (pinfunction "9/RX2/PWM_9") (pintype "bidirectional"))
    )
    (net (code "52") (name "Net-(IC3-Y)") (class "Default")
      (node (ref "IC3") (pin "5") (pinfunction "Y_5") (pintype "bidirectional"))
      (node (ref "SERIAL4") (pin "1") (pinfunction "1_1") (pintype "bidirectional"))
    )
    (net (code "53") (name "Net-(IC3-Z)") (class "Default")
      (node (ref "IC3") (pin "6") (pinfunction "Z_6") (pintype "bidirectional"))
      (node (ref "SERIAL4") (pin "2") (pinfunction "2_2") (pintype "bidirectional"))
    )
    (net (code "54") (name "Net-(IC4-A)") (class "Default")
      (node (ref "IC4") (pin "8") (pinfunction "A_8") (pintype "bidirectional"))
      (node (ref "SERIAL2") (pin "4") (pinfunction "4_4") (pintype "bidirectional"))
    )
    (net (code "55") (name "Net-(IC4-B)") (class "Default")
      (node (ref "IC4") (pin "7") (pinfunction "B_7") (pintype "bidirectional"))
      (node (ref "SERIAL2") (pin "3") (pinfunction "3_3") (pintype "bidirectional"))
    )
    (net (code "56") (name "Net-(IC4-D)") (class "Default")
      (node (ref "IC4") (pin "3") (pinfunction "D_3") (pintype "bidirectional"))
      (node (ref "U$1") (pin "32/A13") (pinfunction "32/A13/TX4_32/A13") (pintype "bidirectional"))
    )
    (net (code "57") (name "Net-(IC4-R)") (class "Default")
      (node (ref "IC4") (pin "2") (pinfunction "R_2") (pintype "bidirectional"))
      (node (ref "U$1") (pin "31/A12") (pinfunction "31/A12/RX4_31/A12") (pintype "bidirectional"))
    )
    (net (code "58") (name "Net-(IC4-Y)") (class "Default")
      (node (ref "IC4") (pin "5") (pinfunction "Y_5") (pintype "bidirectional"))
      (node (ref "SERIAL2") (pin "1") (pinfunction "1_1") (pintype "bidirectional"))
    )
    (net (code "59") (name "Net-(IC4-Z)") (class "Default")
      (node (ref "IC4") (pin "6") (pinfunction "Z_6") (pintype "bidirectional"))
      (node (ref "SERIAL2") (pin "2") (pinfunction "2_2") (pintype "bidirectional"))
    )
    (net (code "60") (name "Net-(IC5-A)") (class "Default")
      (node (ref "IC5") (pin "8") (pinfunction "A_8") (pintype "bidirectional"))
      (node (ref "SERIAL1") (pin "4") (pinfunction "4_4") (pintype "bidirectional"))
    )
    (net (code "61") (name "Net-(IC5-B)") (class "Default")
      (node (ref "IC5") (pin "7") (pinfunction "B_7") (pintype "bidirectional"))
      (node (ref "SERIAL1") (pin "3") (pinfunction "3_3") (pintype "bidirectional"))
    )
    (net (code "62") (name "Net-(IC5-D)") (class "Default")
      (node (ref "IC5") (pin "3") (pinfunction "D_3") (pintype "bidirectional"))
      (node (ref "U$1") (pin "33/A14") (pinfunction "33/A14/TX5/CAN1-TX_33/A14") (pintype "bidirectional"))
    )
    (net (code "63") (name "Net-(IC5-R)") (class "Default")
      (node (ref "IC5") (pin "2") (pinfunction "R_2") (pintype "bidirectional"))
      (node (ref "U$1") (pin "34/A15") (pinfunction "34/A15/RX5/CAN1-RX_34/A15") (pintype "bidirectional"))
    )
    (net (code "64") (name "Net-(IC5-Y)") (class "Default")
      (node (ref "IC5") (pin "5") (pinfunction "Y_5") (pintype "bidirectional"))
      (node (ref "SERIAL1") (pin "1") (pinfunction "1_1") (pintype "bidirectional"))
    )
    (net (code "65") (name "Net-(IC5-Z)") (class "Default")
      (node (ref "IC5") (pin "6") (pinfunction "Z_6") (pintype "bidirectional"))
      (node (ref "SERIAL1") (pin "2") (pinfunction "2_2") (pintype "bidirectional"))
    )
    (net (code "66") (name "Net-(IC6-A1)") (class "Default")
      (node (ref "IC6") (pin "1") (pinfunction "A1_1") (pintype "bidirectional"))
      (node (ref "R2") (pin "1") (pinfunction "1_1") (pintype "passive"))
    )
    (net (code "67") (name "Net-(IC6-A2)") (class "Default")
      (node (ref "IC6") (pin "3") (pinfunction "A2_3") (pintype "bidirectional"))
      (node (ref "U$4") (pin "GND") (pinfunction "GND_GND") (pintype "bidirectional"))
    )
    (net (code "68") (name "Net-(IC6-C1)") (class "Default")
      (node (ref "IC6") (pin "2") (pinfunction "C1_2") (pintype "bidirectional"))
      (node (ref "U$3") (pin "GND") (pinfunction "GND_GND") (pintype "bidirectional"))
    )
    (net (code "69") (name "Net-(IC6-C2)") (class "Default")
      (node (ref "IC6") (pin "4") (pinfunction "C2_4") (pintype "bidirectional"))
      (node (ref "R3") (pin "1") (pinfunction "1_1") (pintype "passive"))
    )
    (net (code "70") (name "Net-(IC7-GND_ISO)") (class "Default")
      (node (ref "C7") (pin "1") (pinfunction "1_1") (pintype "passive"))
      (node (ref "IC7") (pin "5") (pinfunction "GND_ISO_5") (pintype "bidirectional"))
      (node (ref "U$2") (pin "GND") (pinfunction "GND_GND") (pintype "bidirectional"))
      (node (ref "U$5") (pin "GND") (pinfunction "GND_GND") (pintype "bidirectional"))
    )
    (net (code "71") (name "Net-(IC7-VO_A)") (class "Default")
      (node (ref "IC7") (pin "7") (pinfunction "VO_A_7") (pintype "bidirectional"))
      (node (ref "U$5") (pin "S") (pinfunction "OUT_S") (pintype "bidirectional"))
    )
    (net (code "72") (name "Net-(IC7-VO_B)") (class "Default")
      (node (ref "IC7") (pin "6") (pinfunction "VO_B_6") (pintype "bidirectional"))
      (node (ref "U$2") (pin "S") (pinfunction "OUT_S") (pintype "bidirectional"))
    )
    (net (code "73") (name "Net-(IC7-V_ISO)") (class "Default")
      (node (ref "C7") (pin "2") (pinfunction "2_2") (pintype "passive"))
      (node (ref "IC7") (pin "8") (pinfunction "V_ISO_8") (pintype "bidirectional"))
    )
    (net (code "74") (name "Net-(IC9-Pad+VOUT)") (class "Default")
      (node (ref "IC9") (pin "+VOUT") (pinfunction "+VOUT_+VOUT") (pintype "bidirectional"))
      (node (ref "L1") (pin "1") (pinfunction "1_1") (pintype "passive"))
    )
    (net (code "75") (name "Net-(IC9-Pad-VIN)") (class "Default")
      (node (ref "IC9") (pin "-VIN") (pinfunction "-VIN_-VIN") (pintype "bidirectional"))
      (node (ref "J1") (pin "2") (pinfunction "2_2") (pintype "passive"))
    )
    (net (code "76") (name "Net-(IC10-Pad+VOUT)") (class "Default")
      (node (ref "IC10") (pin "+VOUT") (pinfunction "+VOUT_+VOUT") (pintype "bidirectional"))
      (node (ref "L2") (pin "1") (pinfunction "1_1") (pintype "passive"))
    )
    (net (code "77") (name "Net-(IC10-Pad-VIN)") (class "Default")
      (node (ref "IC10") (pin "-VIN") (pinfunction "-VIN_-VIN") (pintype "bidirectional"))
      (node (ref "J2") (pin "2") (pinfunction "2_2") (pintype "passive"))
    )
    (net (code "78") (name "Net-(IC11-Pad+VOUT)") (class "Default")
      (node (ref "IC11") (pin "+VOUT") (pinfunction "+VOUT_+VOUT") (pintype "bidirectional"))
      (node (ref "L3") (pin "1") (pinfunction "1_1") (pintype "passive"))
    )
    (net (code "79") (name "Net-(IC11-Pad-VIN)") (class "Default")
      (node (ref "IC11") (pin "-VIN") (pinfunction "-VIN_-VIN") (pintype "bidirectional"))
      (node (ref "J3") (pin "2") (pinfunction "2_2") (pintype "passive"))
    )
    (net (code "80") (name "Net-(IC12-2IN)") (class "Default")
      (node (ref "IC12") (pin "5") (pinfunction "2IN_5") (pintype "bidirectional"))
      (node (ref "PORT1") (pin "1") (pinfunction "1_1") (pintype "bidirectional"))
    )
    (net (code "81") (name "Net-(IC12-3IN)") (class "Default")
      (node (ref "IC12") (pin "7") (pinfunction "3IN_7") (pintype "bidirectional"))
      (node (ref "PORT2") (pin "1") (pinfunction "1_1") (pintype "bidirectional"))
    )
    (net (code "82") (name "Net-(IC12-4IN)") (class "Default")
      (node (ref "IC12") (pin "9") (pinfunction "4IN_9") (pintype "bidirectional"))
      (node (ref "PORT3") (pin "1") (pinfunction "1_1") (pintype "bidirectional"))
    )
    (net (code "83") (name "Net-(IC12-5IN)") (class "Default")
      (node (ref "IC12") (pin "11") (pinfunction "5IN_11") (pintype "bidirectional"))
      (node (ref "PORT4") (pin "1") (pinfunction "1_1") (pintype "bidirectional"))
    )
    (net (code "84") (name "Net-(U$3-OUT)") (class "Default")
      (node (ref "R2") (pin "2") (pinfunction "2_2") (pintype "passive"))
      (node (ref "U$3") (pin "S") (pinfunction "OUT_S") (pintype "bidirectional"))
    )
    (net (code "85") (name "Net-(U$4-OUT)") (class "Default")
      (node (ref "R3") (pin "2") (pinfunction "2_2") (pintype "passive"))
      (node (ref "U$4") (pin "S") (pinfunction "OUT_S") (pintype "bidirectional"))
    )
    (net (code "86") (name "Net-(U$8-2)") (class "Default")
      (node (ref "R1") (pin "2") (pinfunction "2_2") (pintype "passive"))
      (node (ref "U$8") (pin "P$2") (pinfunction "2_P$2") (pintype "bidirectional"))
    )
    (net (code "87") (name "VCC") (class "Default")
      (node (ref "C1") (pin "1") (pinfunction "1_1") (pintype "passive"))
      (node (ref "C11") (pin "1") (pinfunction "1_1") (pintype "passive"))
      (node (ref "C12") (pin "2") (pinfunction "2_2") (pintype "passive"))
      (node (ref "C13") (pin "1") (pinfunction "1_1") (pintype "passive"))
      (node (ref "C2") (pin "1") (pinfunction "1_1") (pintype "passive"))
      (node (ref "C3") (pin "1") (pinfunction "1_1") (pintype "passive"))
      (node (ref "C4") (pin "1") (pinfunction "1_1") (pintype "passive"))
      (node (ref "C5") (pin "1") (pinfunction "1_1") (pintype "passive"))
      (node (ref "IC1") (pin "1") (pinfunction "VCC_1") (pintype "bidirectional"))
      (node (ref "IC12") (pin "1") (pinfunction "VCC_1") (pintype "bidirectional"))
      (node (ref "IC2") (pin "1") (pinfunction "VCC_1") (pintype "bidirectional"))
      (node (ref "IC3") (pin "1") (pinfunction "VCC_1") (pintype "bidirectional"))
      (node (ref "IC4") (pin "1") (pinfunction "VCC_1") (pintype "bidirectional"))
      (node (ref "IC5") (pin "1") (pinfunction "VCC_1") (pintype "bidirectional"))
      (node (ref "IC6") (pin "8") (pinfunction "CL1_8") (pintype "bidirectional"))
      (node (ref "IC8") (pin "P$2") (pinfunction "P$2_P$2") (pintype "bidirectional"))
      (node (ref "U$1") (pin "3.3V") (pinfunction "3.3V_3.3V") (pintype "power_in"))
      (node (ref "U$1") (pin "3.3V3") (pinfunction "3.3V_3.3V3") (pintype "power_in"))
    )
    (net (code "88") (name "unconnected-(IC8-PadP$1)") (class "Default")
      (node (ref "IC8") (pin "P$1") (pinfunction "P$1_P$1") (pintype "bidirectional"))
    )
    (net (code "89") (name "unconnected-(IC8-PadP$14)") (class "Default")
      (node (ref "IC8") (pin "P$14") (pinfunction "P$14_P$14") (pintype "bidirectional"))
    )
    (net (code "90") (name "unconnected-(IC8-PadP$16)") (class "Default")
      (node (ref "IC8") (pin "P$16") (pinfunction "P$16_P$16") (pintype "bidirectional"))
    )
    (net (code "91") (name "unconnected-(IC8-PadP$17)") (class "Default")
      (node (ref "IC8") (pin "P$17") (pinfunction "P$17_P$17") (pintype "bidirectional"))
    )
    (net (code "92") (name "unconnected-(IC8-PadP$18)") (class "Default")
      (node (ref "IC8") (pin "P$18") (pinfunction "P$18_P$18") (pintype "bidirectional"))
    )
    (net (code "93") (name "unconnected-(IC8-PadP$20)") (class "Default")
      (node (ref "IC8") (pin "P$20") (pinfunction "P$20_P$20") (pintype "bidirectional"))
    )
    (net (code "94") (name "unconnected-(IC9-PadNC)") (class "Default")
      (node (ref "IC9") (pin "NC") (pinfunction "NC_NC") (pintype "bidirectional"))
    )
    (net (code "95") (name "unconnected-(IC10-PadNC)") (class "Default")
      (node (ref "IC10") (pin "NC") (pinfunction "NC_NC") (pintype "bidirectional"))
    )
    (net (code "96") (name "unconnected-(IC11-PadNC)") (class "Default")
      (node (ref "IC11") (pin "NC") (pinfunction "NC_NC") (pintype "bidirectional"))
    )
    (net (code "97") (name "unconnected-(IC12-1IN-Pad3)") (class "Default")
      (node (ref "IC12") (pin "3") (pinfunction "1IN_3") (pintype "bidirectional"))
    )
    (net (code "98") (name "unconnected-(IC12-1OUT-Pad2)") (class "Default")
      (node (ref "IC12") (pin "2") (pinfunction "1OUT_2") (pintype "bidirectional"))
    )
    (net (code "99") (name "unconnected-(IC12-6IN-Pad14)") (class "Default")
      (node (ref "IC12") (pin "14") (pinfunction "6IN_14") (pintype "bidirectional"))
    )
    (net (code "100") (name "unconnected-(IC12-6OUT-Pad15)") (class "Default")
      (node (ref "IC12") (pin "15") (pinfunction "6OUT_15") (pintype "bidirectional"))
    )
    (net (code "101") (name "unconnected-(IC12-NC-Pad16)") (class "Default")
      (node (ref "IC12") (pin "16") (pinfunction "NC_16") (pintype "bidirectional"))
    )
    (net (code "102") (name "unconnected-(IC12-NC2-Pad13)") (class "Default")
      (node (ref "IC12") (pin "13") (pinfunction "NC2_13") (pintype "bidirectional"))
    )
    (net (code "103") (name "unconnected-(PORT1-Pad2)") (class "Default")
      (node (ref "PORT1") (pin "2") (pinfunction "2_2") (pintype "bidirectional"))
    )
    (net (code "104") (name "unconnected-(PORT1-Pad8)") (class "Default")
      (node (ref "PORT1") (pin "8") (pinfunction "8_8") (pintype "bidirectional"))
    )
    (net (code "105") (name "unconnected-(PORT2-Pad2)") (class "Default")
      (node (ref "PORT2") (pin "2") (pinfunction "2_2") (pintype "bidirectional"))
    )
    (net (code "106") (name "unconnected-(PORT2-Pad8)") (class "Default")
      (node (ref "PORT2") (pin "8") (pinfunction "8_8") (pintype "bidirectional"))
    )
    (net (code "107") (name "unconnected-(PORT3-Pad2)") (class "Default")
      (node (ref "PORT3") (pin "2") (pinfunction "2_2") (pintype "bidirectional"))
    )
    (net (code "108") (name "unconnected-(PORT3-Pad8)") (class "Default")
      (node (ref "PORT3") (pin "8") (pinfunction "8_8") (pintype "bidirectional"))
    )
    (net (code "109") (name "unconnected-(PORT4-Pad2)") (class "Default")
      (node (ref "PORT4") (pin "2") (pinfunction "2_2") (pintype "bidirectional"))
    )
    (net (code "110") (name "unconnected-(PORT4-Pad8)") (class "Default")
      (node (ref "PORT4") (pin "8") (pinfunction "8_8") (pintype "bidirectional"))
    )
    (net (code "111") (name "unconnected-(SERIAL1-Pad5)") (class "Default")
      (node (ref "SERIAL1") (pin "5") (pinfunction "5_5") (pintype "bidirectional"))
    )
    (net (code "112") (name "unconnected-(SERIAL1-Pad6)") (class "Default")
      (node (ref "SERIAL1") (pin "6") (pinfunction "6_6") (pintype "bidirectional"))
    )
    (net (code "113") (name "unconnected-(SERIAL1-Pad7)") (class "Default")
      (node (ref "SERIAL1") (pin "7") (pinfunction "7_7") (pintype "bidirectional"))
    )
    (net (code "114") (name "unconnected-(SERIAL1-Pad8)") (class "Default")
      (node (ref "SERIAL1") (pin "8") (pinfunction "8_8") (pintype "bidirectional"))
    )
    (net (code "115") (name "unconnected-(SERIAL2-Pad5)") (class "Default")
      (node (ref "SERIAL2") (pin "5") (pinfunction "5_5") (pintype "bidirectional"))
    )
    (net (code "116") (name "unconnected-(SERIAL2-Pad6)") (class "Default")
      (node (ref "SERIAL2") (pin "6") (pinfunction "6_6") (pintype "bidirectional"))
    )
    (net (code "117") (name "unconnected-(SERIAL2-Pad7)") (class "Default")
      (node (ref "SERIAL2") (pin "7") (pinfunction "7_7") (pintype "bidirectional"))
    )
    (net (code "118") (name "unconnected-(SERIAL2-Pad8)") (class "Default")
      (node (ref "SERIAL2") (pin "8") (pinfunction "8_8") (pintype "bidirectional"))
    )
    (net (code "119") (name "unconnected-(SERIAL3-Pad7)") (class "Default")
      (node (ref "SERIAL3") (pin "7") (pinfunction "7_7") (pintype "bidirectional"))
    )
    (net (code "120") (name "unconnected-(SERIAL3-Pad8)") (class "Default")
      (node (ref "SERIAL3") (pin "8") (pinfunction "8_8") (pintype "bidirectional"))
    )
    (net (code "121") (name "unconnected-(SERIAL4-Pad7)") (class "Default")
      (node (ref "SERIAL4") (pin "7") (pinfunction "7_7") (pintype "bidirectional"))
    )
    (net (code "122") (name "unconnected-(SERIAL4-Pad8)") (class "Default")
      (node (ref "SERIAL4") (pin "8") (pinfunction "8_8") (pintype "bidirectional"))
    )
    (net (code "123") (name "unconnected-(SERIAL5-Pad7)") (class "Default")
      (node (ref "SERIAL5") (pin "7") (pinfunction "7_7") (pintype "bidirectional"))
    )
    (net (code "124") (name "unconnected-(SERIAL5-Pad8)") (class "Default")
      (node (ref "SERIAL5") (pin "8") (pinfunction "8_8") (pintype "bidirectional"))
    )
    (net (code "125") (name "unconnected-(U$1-11{slash}MOSI0-Pad11)") (class "Default")
      (node (ref "U$1") (pin "11") (pinfunction "11/MOSI0_11") (pintype "bidirectional"))
    )
    (net (code "126") (name "unconnected-(U$1-12{slash}MISO0-Pad12)") (class "Default")
      (node (ref "U$1") (pin "12") (pinfunction "12/MISO0_12") (pintype "bidirectional"))
    )
    (net (code "127") (name "unconnected-(U$1-13{slash}SCK0{slash}LED-Pad13)") (class "Default")
      (node (ref "U$1") (pin "13") (pinfunction "13/SCK0/LED_13") (pintype "bidirectional"))
    )
    (net (code "128") (name "unconnected-(U$1-29{slash}T{slash}PWM-Pad29)") (class "Default")
      (node (ref "U$1") (pin "29") (pinfunction "29/T/PWM_29") (pintype "bidirectional"))
    )
    (net (code "129") (name "unconnected-(U$1-30{slash}T{slash}PWM-Pad30)") (class "Default")
      (node (ref "U$1") (pin "30") (pinfunction "30/T/PWM_30") (pintype "bidirectional"))
    )
    (net (code "130") (name "unconnected-(U$1-A21{slash}DAC0-PadA21)") (class "Default")
      (node (ref "U$1") (pin "A21") (pinfunction "A21/DAC0_A21") (pintype "bidirectional"))
    )
    (net (code "131") (name "unconnected-(U$1-A22{slash}DAC1-PadA22)") (class "Default")
      (node (ref "U$1") (pin "A22") (pinfunction "A22/DAC1_A22") (pintype "bidirectional"))
    )
    (net (code "132") (name "unconnected-(U$1-Pad24)") (class "Default")
      (node (ref "U$1") (pin "24") (pinfunction "24_24") (pintype "bidirectional"))
    )
    (net (code "133") (name "unconnected-(U$1-Pad25)") (class "Default")
      (node (ref "U$1") (pin "25") (pinfunction "25_25") (pintype "bidirectional"))
    )
    (net (code "134") (name "unconnected-(U$1-Pad26)") (class "Default")
      (node (ref "U$1") (pin "26") (pinfunction "26_26") (pintype "bidirectional"))
    )
    (net (code "135") (name "unconnected-(U$1-Pad27)") (class "Default")
      (node (ref "U$1") (pin "27") (pinfunction "27_27") (pintype "bidirectional"))
    )
    (net (code "136") (name "unconnected-(U$1-Pad28)") (class "Default")
      (node (ref "U$1") (pin "28") (pinfunction "28_28") (pintype "bidirectional"))
    )
  )
)
